# WaldoRevE.net
KiCad netlist of a schematic drawn in EAGLE
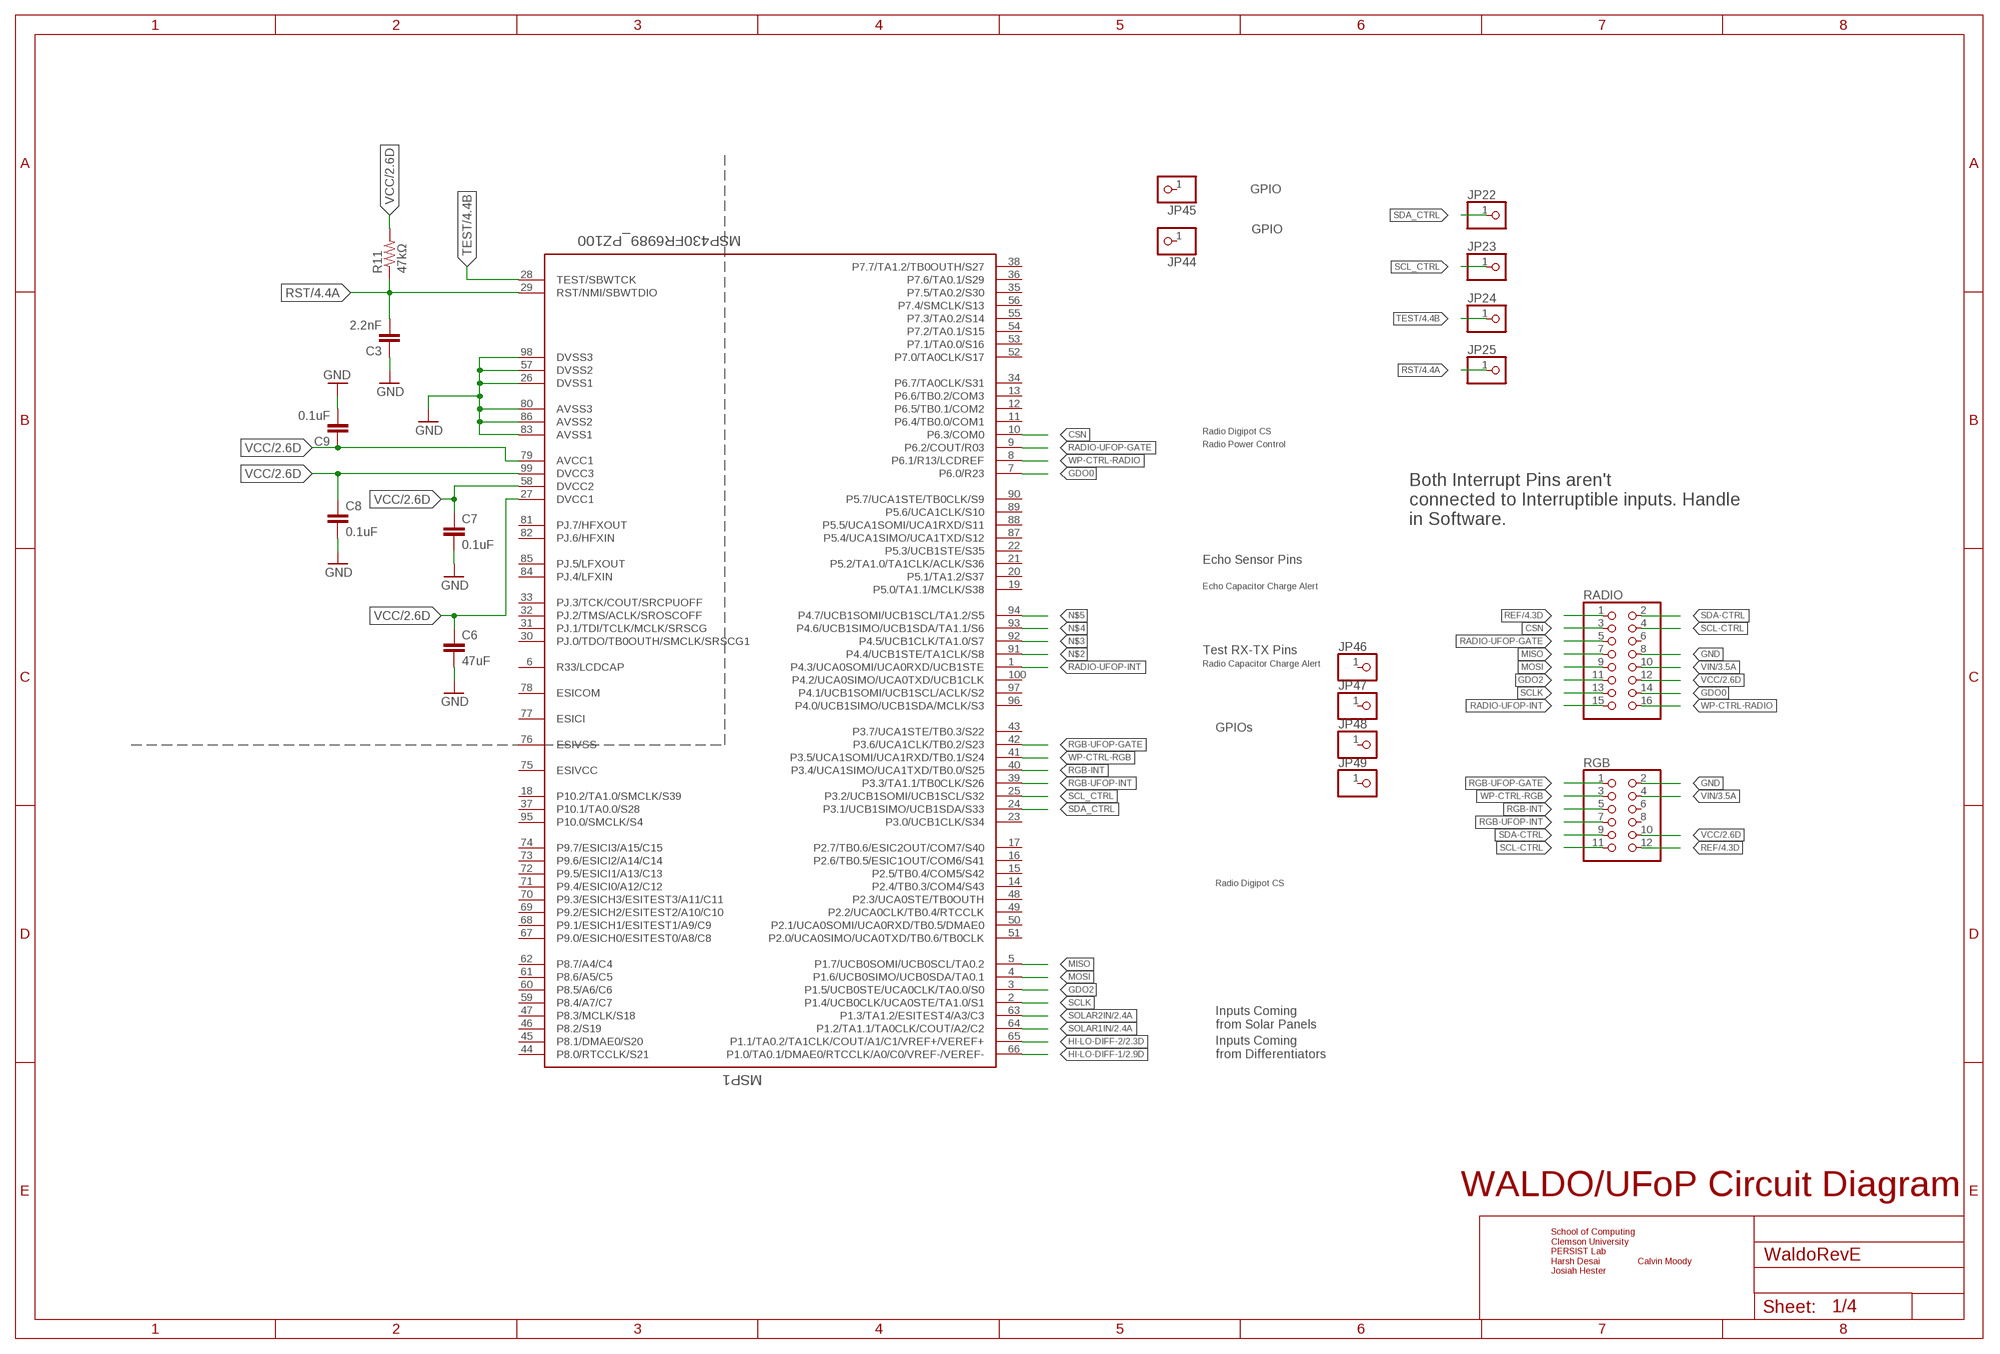
[diagram p0: schematic, sheet 1]
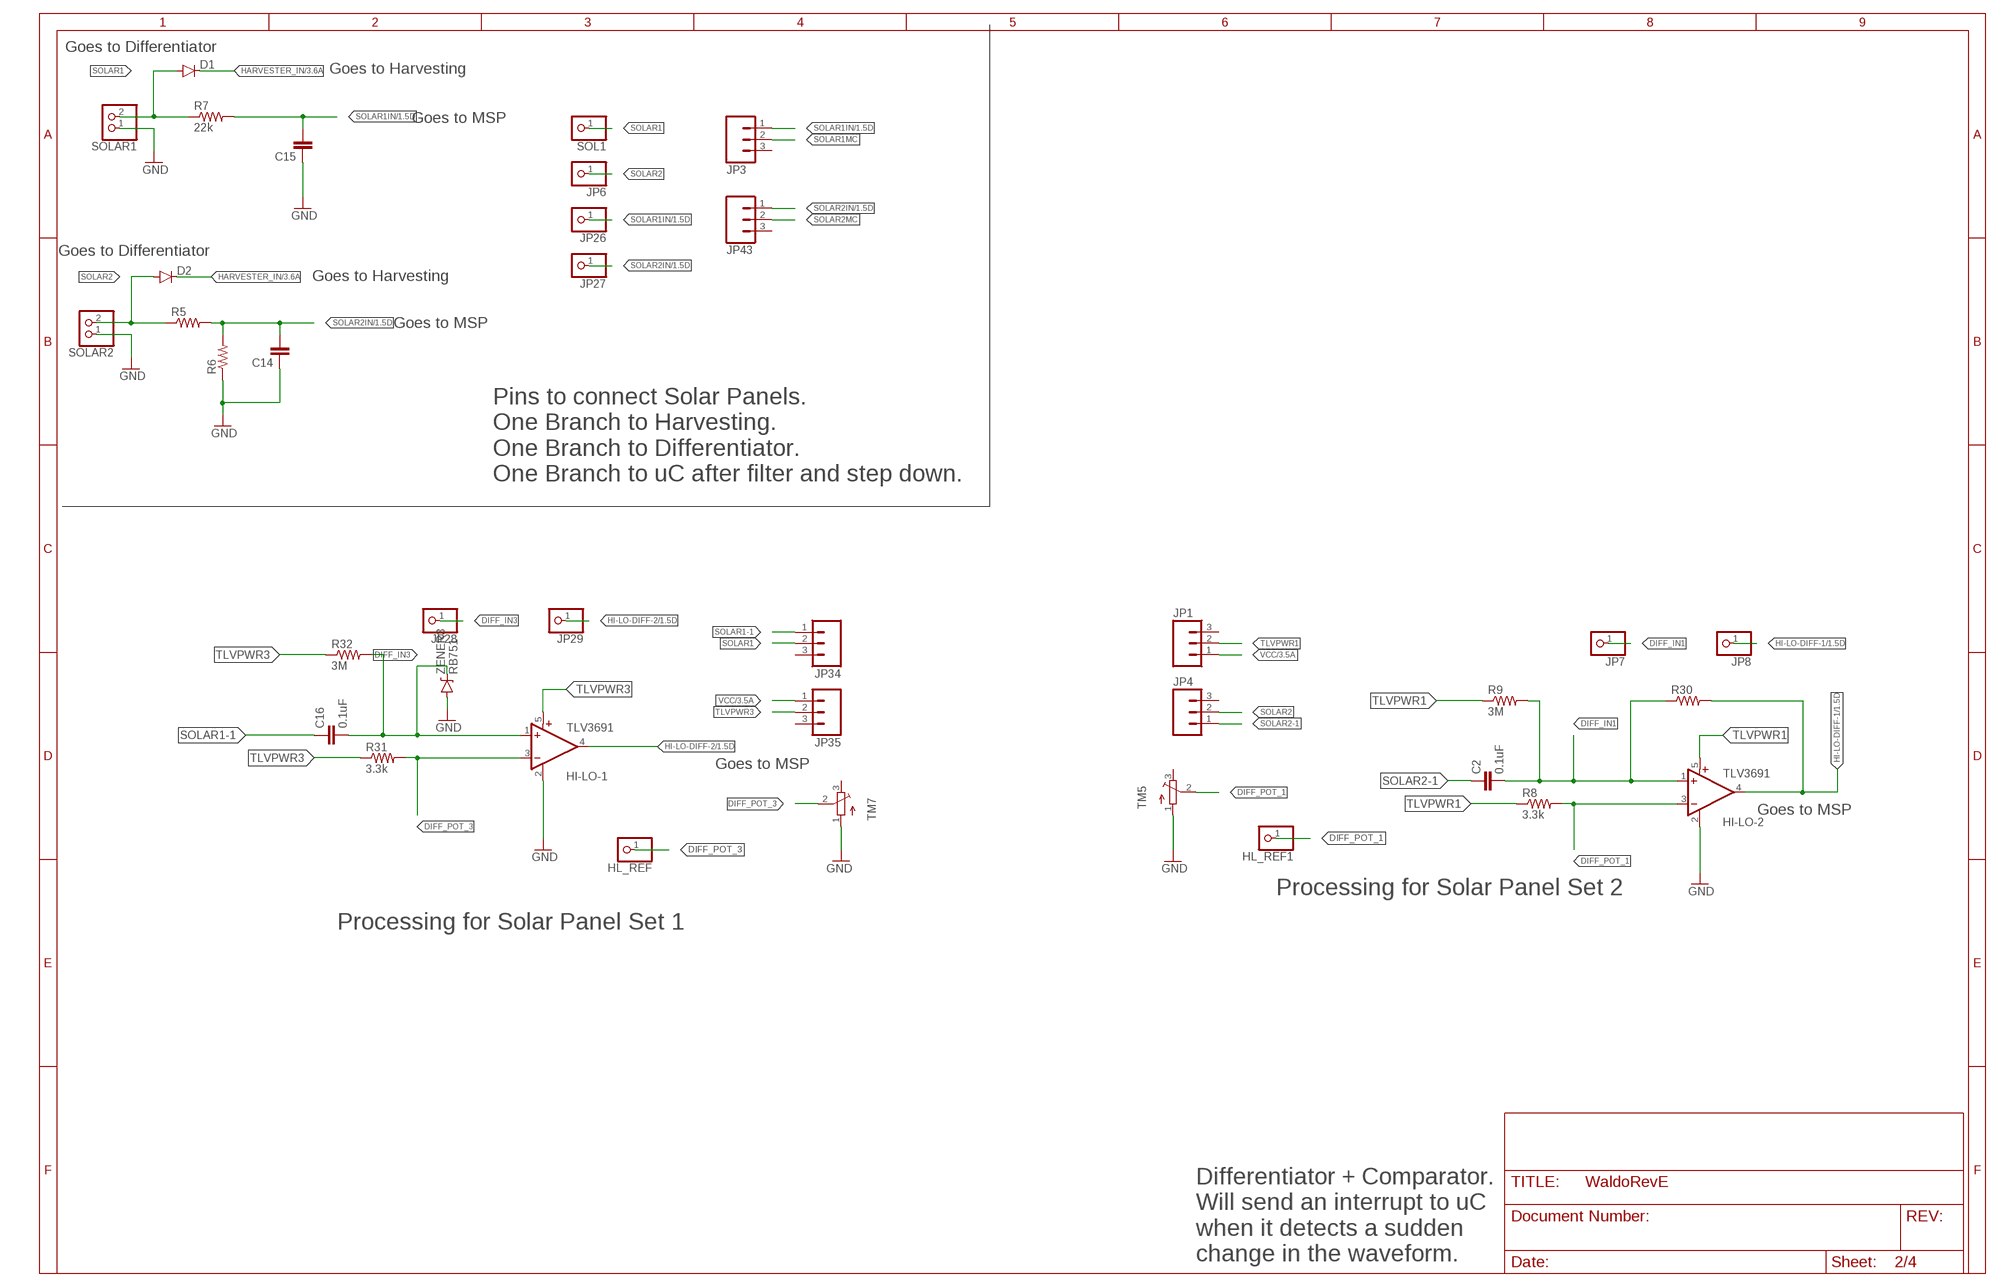
[diagram p1: schematic, sheet 2]
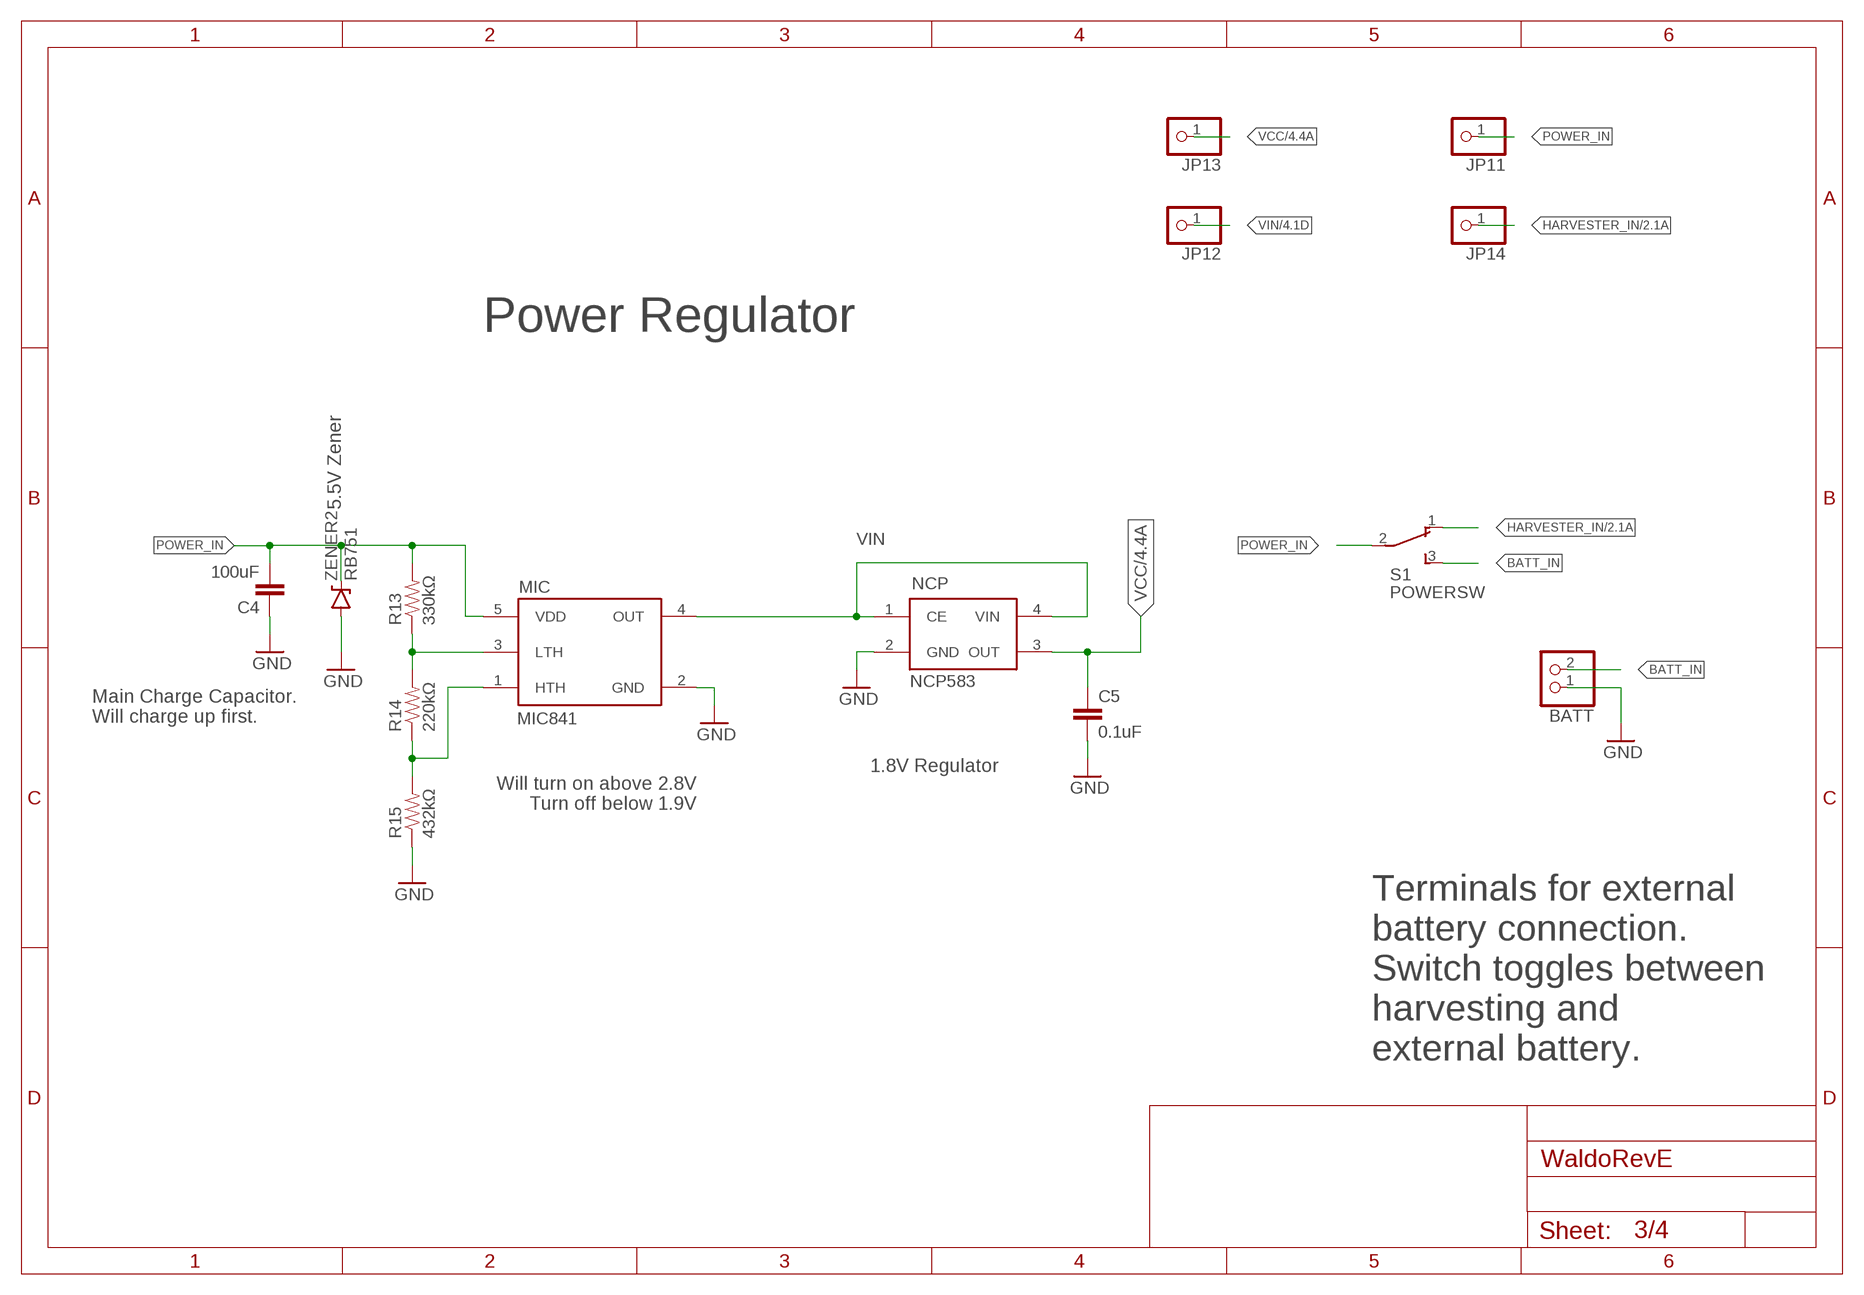
[diagram p2: schematic, sheet 3]
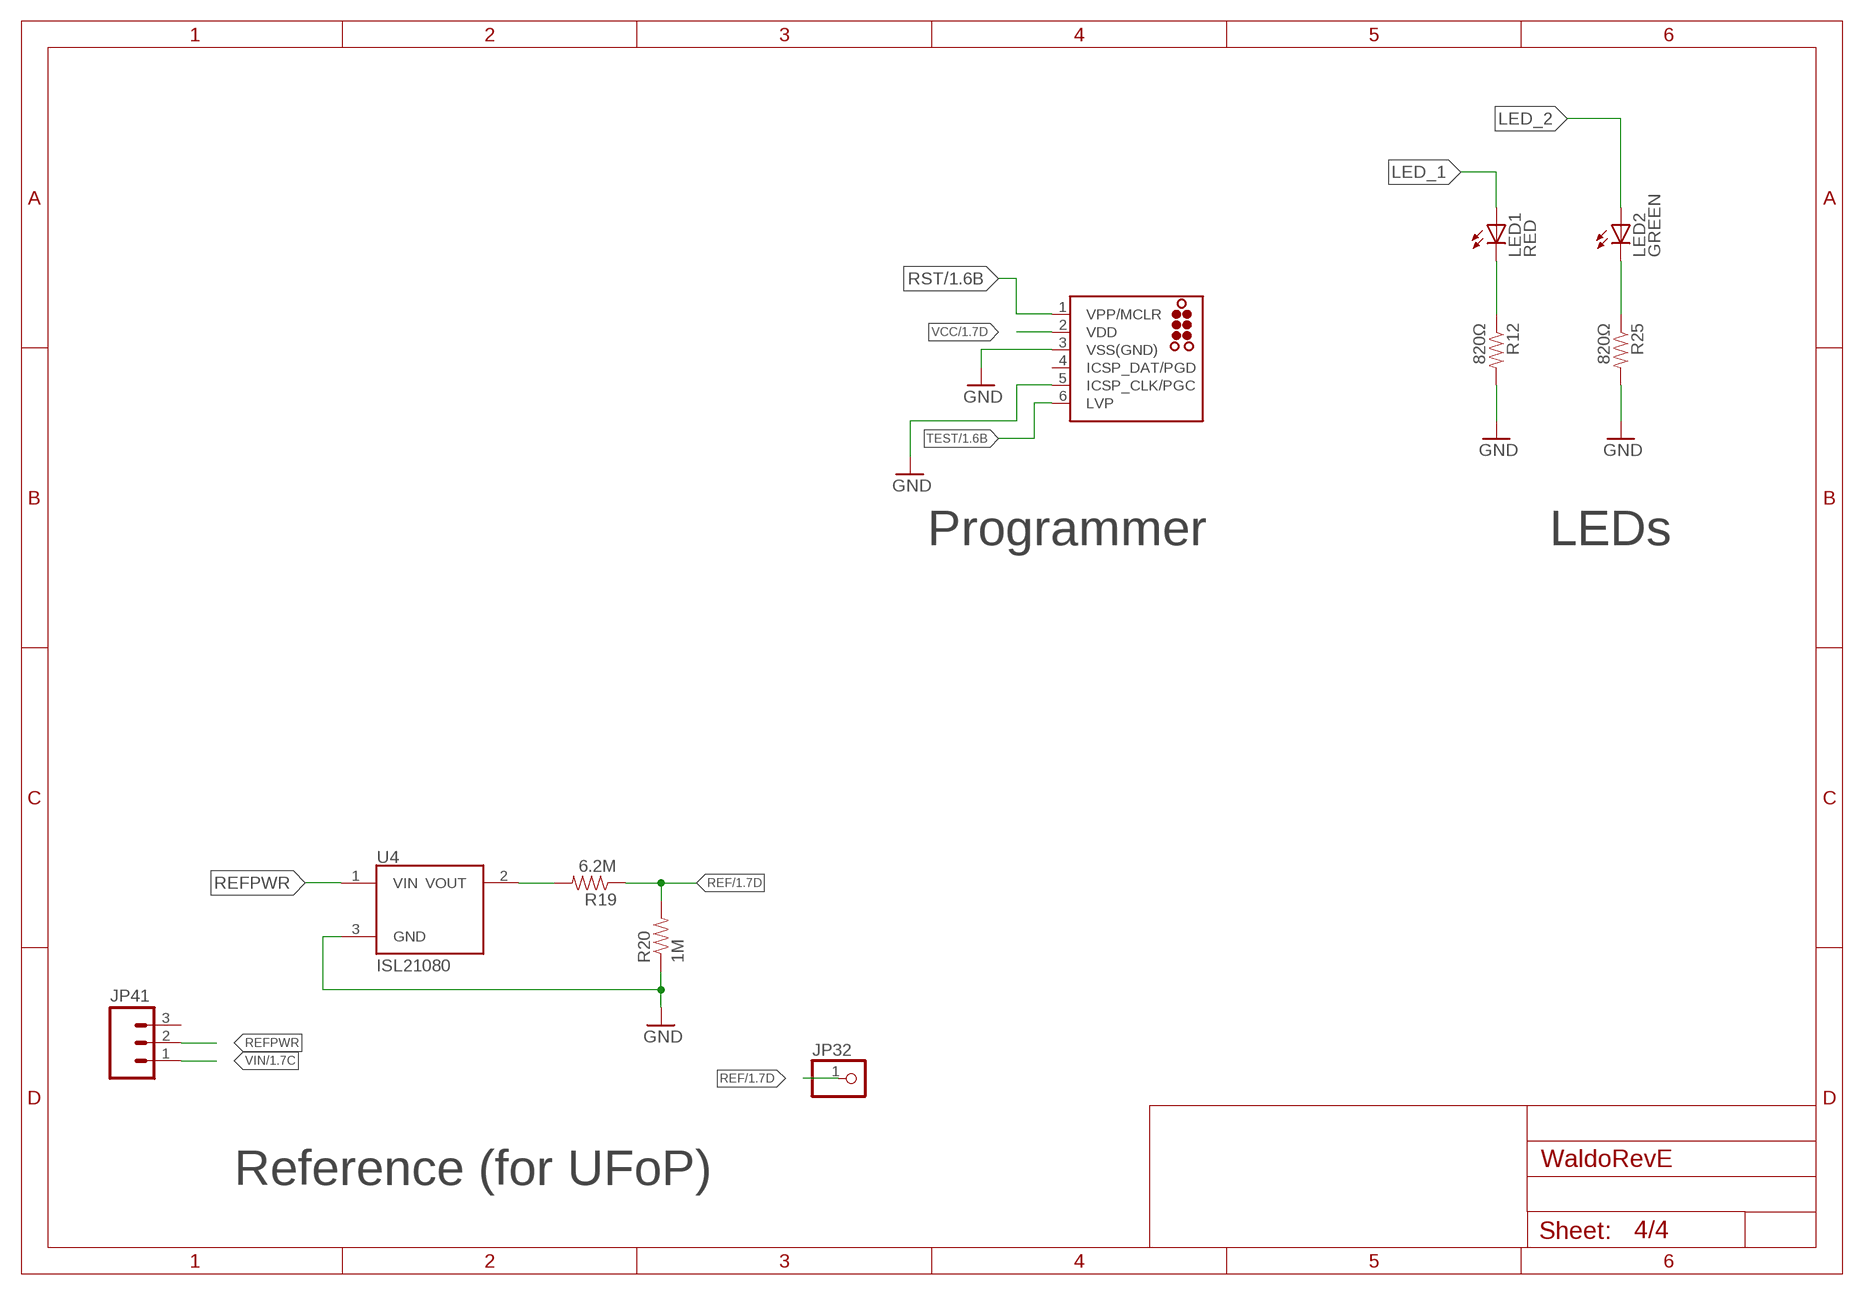
[diagram p3: schematic, sheet 4]

(export (version "E")
  (design (tool "Eeschema 10.0.6"))
  (components
    (comp (ref "C2")
      (value "0.1uF")
      (footprint "eagle-import:0805")
      (libsource (lib "eagle-import") (part "CAP0805"))
    )
    (comp (ref "C14")
      (value "CAP0805")
      (footprint "eagle-import:0805")
      (libsource (lib "eagle-import") (part "CAP0805"))
    )
    (comp (ref "C15")
      (value "CAP0805")
      (footprint "eagle-import:0805")
      (libsource (lib "eagle-import") (part "CAP0805"))
    )
    (comp (ref "C16")
      (value "0.1uF")
      (footprint "eagle-import:0805")
      (libsource (lib "eagle-import") (part "CAP0805"))
    )
    (comp (ref "D1")
      (value "DIODESOD523")
      (footprint "eagle-import:SOD523")
      (libsource (lib "eagle-import") (part "DIODESOD523"))
    )
    (comp (ref "D2")
      (value "DIODESOD523")
      (footprint "eagle-import:SOD523")
      (libsource (lib "eagle-import") (part "DIODESOD523"))
    )
    (comp (ref "HI-LO-1")
      (value "TLV3691")
      (footprint "eagle-import:SC70-5")
      (libsource (lib "eagle-import") (part "TLV3691"))
    )
    (comp (ref "HI-LO-2")
      (value "TLV3691")
      (footprint "eagle-import:SC70-5")
      (libsource (lib "eagle-import") (part "TLV3691"))
    )
    (comp (ref "HL_REF")
      (value "PINHD-1X1")
      (footprint "eagle-import:1X01")
      (libsource (lib "eagle-import") (part "PINHD-1X1"))
    )
    (comp (ref "HL_REF1")
      (value "PINHD-1X1")
      (footprint "eagle-import:1X01")
      (libsource (lib "eagle-import") (part "PINHD-1X1"))
    )
    (comp (ref "JP1")
      (value "M03")
      (footprint "eagle-import:1X03-1.27MM")
      (libsource (lib "eagle-import") (part "M03"))
    )
    (comp (ref "JP3")
      (value "M03")
      (footprint "eagle-import:1X03-1.27MM")
      (libsource (lib "eagle-import") (part "M03"))
    )
    (comp (ref "JP4")
      (value "M03")
      (footprint "eagle-import:1X03-1.27MM")
      (libsource (lib "eagle-import") (part "M03"))
    )
    (comp (ref "JP6")
      (value "PINHD-1X1")
      (footprint "eagle-import:1X01")
      (libsource (lib "eagle-import") (part "PINHD-1X1"))
    )
    (comp (ref "JP7")
      (value "PINHD-1X1")
      (footprint "eagle-import:1X01")
      (libsource (lib "eagle-import") (part "PINHD-1X1"))
    )
    (comp (ref "JP8")
      (value "PINHD-1X1")
      (footprint "eagle-import:1X01")
      (libsource (lib "eagle-import") (part "PINHD-1X1"))
    )
    (comp (ref "JP26")
      (value "PINHD-1X1")
      (footprint "eagle-import:1X01")
      (libsource (lib "eagle-import") (part "PINHD-1X1"))
    )
    (comp (ref "JP27")
      (value "PINHD-1X1")
      (footprint "eagle-import:1X01")
      (libsource (lib "eagle-import") (part "PINHD-1X1"))
    )
    (comp (ref "JP28")
      (value "PINHD-1X1")
      (footprint "eagle-import:1X01")
      (libsource (lib "eagle-import") (part "PINHD-1X1"))
    )
    (comp (ref "JP29")
      (value "PINHD-1X1")
      (footprint "eagle-import:1X01")
      (libsource (lib "eagle-import") (part "PINHD-1X1"))
    )
    (comp (ref "JP34")
      (value "M03")
      (footprint "eagle-import:1X03-1.27MM")
      (libsource (lib "eagle-import") (part "M03"))
    )
    (comp (ref "JP35")
      (value "M03")
      (footprint "eagle-import:1X03-1.27MM")
      (libsource (lib "eagle-import") (part "M03"))
    )
    (comp (ref "JP43")
      (value "M03")
      (footprint "eagle-import:1X03-1.27MM")
      (libsource (lib "eagle-import") (part "M03"))
    )
    (comp (ref "R5")
      (value "RESISTOR0805-RES")
      (footprint "eagle-import:0805")
      (libsource (lib "eagle-import") (part "RESISTOR0805-RES"))
    )
    (comp (ref "R6")
      (value "RESISTOR0805-RES")
      (footprint "eagle-import:0805")
      (libsource (lib "eagle-import") (part "RESISTOR0805-RES"))
    )
    (comp (ref "R7")
      (value "22k")
      (footprint "eagle-import:0805")
      (libsource (lib "eagle-import") (part "RESISTOR0805-RES"))
    )
    (comp (ref "R8")
      (value "3.3k")
      (footprint "eagle-import:0805")
      (libsource (lib "eagle-import") (part "RESISTOR0805-RES"))
    )
    (comp (ref "R9")
      (value "3M")
      (footprint "eagle-import:0805")
      (libsource (lib "eagle-import") (part "RESISTOR0805-RES"))
    )
    (comp (ref "R30")
      (value "RESISTOR0805-RES")
      (footprint "eagle-import:0805")
      (libsource (lib "eagle-import") (part "RESISTOR0805-RES"))
    )
    (comp (ref "R31")
      (value "3.3k")
      (footprint "eagle-import:0805")
      (libsource (lib "eagle-import") (part "RESISTOR0805-RES"))
    )
    (comp (ref "R32")
      (value "3M")
      (footprint "eagle-import:0805")
      (libsource (lib "eagle-import") (part "RESISTOR0805-RES"))
    )
    (comp (ref "SOL1")
      (value "PINHD-1X1")
      (footprint "eagle-import:1X01")
      (libsource (lib "eagle-import") (part "PINHD-1X1"))
    )
    (comp (ref "SOLAR1")
      (value "PINHD-1X2")
      (footprint "eagle-import:1X02")
      (libsource (lib "eagle-import") (part "PINHD-1X2"))
    )
    (comp (ref "SOLAR2")
      (value "PINHD-1X2")
      (footprint "eagle-import:1X02")
      (libsource (lib "eagle-import") (part "PINHD-1X2"))
    )
    (comp (ref "TM5")
      (value "TRIMPOTTC33X")
      (footprint "eagle-import:TC33X")
      (libsource (lib "eagle-import") (part "TRIMPOTTC33X"))
    )
    (comp (ref "TM7")
      (value "TRIMPOTTC33X")
      (footprint "eagle-import:TC33X")
      (libsource (lib "eagle-import") (part "TRIMPOTTC33X"))
    )
    (comp (ref "ZENER3")
      (value "RB751")
      (footprint "eagle-import:SOD-523")
      (libsource (lib "eagle-import") (part "DIODE-ZENER"))
    )
    (comp (ref "C3")
      (value "2.2nF")
      (footprint "eagle-import:0805")
      (libsource (lib "eagle-import") (part "CAP0805"))
    )
    (comp (ref "C6")
      (value "47uF")
      (footprint "eagle-import:0805")
      (libsource (lib "eagle-import") (part "CAP0805"))
    )
    (comp (ref "C7")
      (value "0.1uF")
      (footprint "eagle-import:0805")
      (libsource (lib "eagle-import") (part "CAP0805"))
    )
    (comp (ref "C8")
      (value "0.1uF")
      (footprint "eagle-import:0805")
      (libsource (lib "eagle-import") (part "CAP0805"))
    )
    (comp (ref "C9")
      (value "0.1uF")
      (footprint "eagle-import:0805")
      (libsource (lib "eagle-import") (part "CAP0805"))
    )
    (comp (ref "JP22")
      (value "PINHD-1X1")
      (footprint "eagle-import:1X01")
      (libsource (lib "eagle-import") (part "PINHD-1X1"))
    )
    (comp (ref "JP23")
      (value "PINHD-1X1")
      (footprint "eagle-import:1X01")
      (libsource (lib "eagle-import") (part "PINHD-1X1"))
    )
    (comp (ref "JP24")
      (value "PINHD-1X1")
      (footprint "eagle-import:1X01")
      (libsource (lib "eagle-import") (part "PINHD-1X1"))
    )
    (comp (ref "JP25")
      (value "PINHD-1X1")
      (footprint "eagle-import:1X01")
      (libsource (lib "eagle-import") (part "PINHD-1X1"))
    )
    (comp (ref "JP44")
      (value "PINHD-1X1")
      (footprint "eagle-import:1X01")
      (libsource (lib "eagle-import") (part "PINHD-1X1"))
    )
    (comp (ref "JP45")
      (value "PINHD-1X1")
      (footprint "eagle-import:1X01")
      (libsource (lib "eagle-import") (part "PINHD-1X1"))
    )
    (comp (ref "JP46")
      (value "PINHD-1X1")
      (footprint "eagle-import:1X01")
      (libsource (lib "eagle-import") (part "PINHD-1X1"))
    )
    (comp (ref "JP47")
      (value "PINHD-1X1")
      (footprint "eagle-import:1X01")
      (libsource (lib "eagle-import") (part "PINHD-1X1"))
    )
    (comp (ref "JP48")
      (value "PINHD-1X1")
      (footprint "eagle-import:1X01")
      (libsource (lib "eagle-import") (part "PINHD-1X1"))
    )
    (comp (ref "JP49")
      (value "PINHD-1X1")
      (footprint "eagle-import:1X01")
      (libsource (lib "eagle-import") (part "PINHD-1X1"))
    )
    (comp (ref "MSP1")
      (value "MSP430FR6989_PZ100")
      (footprint "eagle-import:PZ100")
      (libsource (lib "eagle-import") (part "MSP430FR6989_PZ100"))
    )
    (comp (ref "R11")
      (value "47kΩ")
      (footprint "eagle-import:0805")
      (libsource (lib "eagle-import") (part "RESISTOR0805-RES"))
    )
    (comp (ref "RADIO")
      (value "PINHD-2X8/90")
      (footprint "eagle-import:2X08_90")
      (libsource (lib "eagle-import") (part "PINHD-2X8/90"))
    )
    (comp (ref "RGB")
      (value "PINHD-2X6/90")
      (footprint "eagle-import:2X06_90")
      (libsource (lib "eagle-import") (part "PINHD-2X6/90"))
    )
    (comp (ref "J2")
      (value "TC2030-MCP-NL")
      (footprint "eagle-import:TC2030-MCP-NL")
      (libsource (lib "eagle-import") (part "TC2030-MCP-NL"))
    )
    (comp (ref "JP32")
      (value "PINHD-1X1")
      (footprint "eagle-import:1X01")
      (libsource (lib "eagle-import") (part "PINHD-1X1"))
    )
    (comp (ref "JP41")
      (value "M03")
      (footprint "eagle-import:1X03-1.27MM")
      (libsource (lib "eagle-import") (part "M03"))
    )
    (comp (ref "LED1")
      (value "RED")
      (footprint "eagle-import:CHIP-LED0805")
      (libsource (lib "eagle-import") (part "LEDCHIP-LED0805"))
    )
    (comp (ref "LED2")
      (value "GREEN")
      (footprint "eagle-import:CHIP-LED0805")
      (libsource (lib "eagle-import") (part "LEDCHIP-LED0805"))
    )
    (comp (ref "R12")
      (value "820Ω")
      (footprint "eagle-import:0805")
      (libsource (lib "eagle-import") (part "RESISTOR0805-RES"))
    )
    (comp (ref "R19")
      (value "6.2M")
      (footprint "eagle-import:0805")
      (libsource (lib "eagle-import") (part "RESISTOR0805-RES"))
    )
    (comp (ref "R20")
      (value "1M")
      (footprint "eagle-import:0805")
      (libsource (lib "eagle-import") (part "RESISTOR0805-RES"))
    )
    (comp (ref "R25")
      (value "820Ω")
      (footprint "eagle-import:0805")
      (libsource (lib "eagle-import") (part "RESISTOR0805-RES"))
    )
    (comp (ref "U4")
      (value "ISL21080")
      (footprint "eagle-import:SOT-23")
      (libsource (lib "eagle-import") (part "ISL21080"))
    )
    (comp (ref "BATT")
      (value "PINHD-1X2")
      (footprint "eagle-import:1X02")
      (libsource (lib "eagle-import") (part "PINHD-1X2"))
    )
    (comp (ref "C4")
      (value "100uF")
      (footprint "eagle-import:0805")
      (libsource (lib "eagle-import") (part "CAP0805"))
    )
    (comp (ref "C5")
      (value "0.1uF")
      (footprint "eagle-import:0805")
      (libsource (lib "eagle-import") (part "CAP0805"))
    )
    (comp (ref "JP11")
      (value "PINHD-1X1")
      (footprint "eagle-import:1X01")
      (libsource (lib "eagle-import") (part "PINHD-1X1"))
    )
    (comp (ref "JP12")
      (value "PINHD-1X1")
      (footprint "eagle-import:1X01")
      (libsource (lib "eagle-import") (part "PINHD-1X1"))
    )
    (comp (ref "JP13")
      (value "PINHD-1X1")
      (footprint "eagle-import:1X01")
      (libsource (lib "eagle-import") (part "PINHD-1X1"))
    )
    (comp (ref "JP14")
      (value "PINHD-1X1")
      (footprint "eagle-import:1X01")
      (libsource (lib "eagle-import") (part "PINHD-1X1"))
    )
    (comp (ref "MIC")
      (value "MIC841")
      (footprint "eagle-import:SC70-5")
      (libsource (lib "eagle-import") (part "MIC841"))
    )
    (comp (ref "NCP")
      (value "NCP583")
      (footprint "eagle-import:SC82-AB_1PRIMARY")
      (libsource (lib "eagle-import") (part "NCP583"))
    )
    (comp (ref "R13")
      (value "330kΩ")
      (footprint "eagle-import:0805")
      (libsource (lib "eagle-import") (part "RESISTOR0805-RES"))
    )
    (comp (ref "R14")
      (value "220kΩ")
      (footprint "eagle-import:0805")
      (libsource (lib "eagle-import") (part "RESISTOR0805-RES"))
    )
    (comp (ref "R15")
      (value "432kΩ")
      (footprint "eagle-import:0805")
      (libsource (lib "eagle-import") (part "RESISTOR0805-RES"))
    )
    (comp (ref "S1")
      (value "POWERSW")
      (footprint "eagle-import:TL3XYO")
      (libsource (lib "eagle-import") (part "POWERSW"))
    )
    (comp (ref "ZENER2")
      (value "RB751")
      (footprint "eagle-import:SOD-523")
      (libsource (lib "eagle-import") (part "DIODE-ZENER"))
    )
  )
  (nets
    (net (code "1") (name "BATT_IN") (class "Default")
      (node (ref "BATT") (pin "2") (pinfunction "2_2") (pintype "passive"))
      (node (ref "S1") (pin "3") (pinfunction "S_3") (pintype "passive"))
    )
    (net (code "2") (name "CSN") (class "Default")
      (node (ref "MSP1") (pin "10") (pinfunction "P6.3/COM0_10") (pintype "bidirectional"))
      (node (ref "RADIO") (pin "3") (pinfunction "3_3") (pintype "passive"))
    )
    (net (code "3") (name "DIFF_IN1") (class "Default")
      (node (ref "C2") (pin "2") (pinfunction "2_2") (pintype "passive"))
      (node (ref "HI-LO-2") (pin "1") (pinfunction "+IN_1") (pintype "input"))
      (node (ref "JP7") (pin "1") (pinfunction "1_1") (pintype "passive"))
      (node (ref "R30") (pin "1") (pinfunction "1_1") (pintype "passive"))
      (node (ref "R9") (pin "2") (pinfunction "2_2") (pintype "passive"))
    )
    (net (code "4") (name "DIFF_IN3") (class "Default")
      (node (ref "C16") (pin "2") (pinfunction "2_2") (pintype "passive"))
      (node (ref "HI-LO-1") (pin "1") (pinfunction "+IN_1") (pintype "input"))
      (node (ref "JP28") (pin "1") (pinfunction "1_1") (pintype "passive"))
      (node (ref "R32") (pin "2") (pinfunction "2_2") (pintype "passive"))
      (node (ref "ZENER3") (pin "CATHODE") (pinfunction "C_CATHODE") (pintype "passive"))
    )
    (net (code "5") (name "DIFF_POT_1") (class "Default")
      (node (ref "HI-LO-2") (pin "3") (pinfunction "-IN_3") (pintype "input"))
      (node (ref "HL_REF1") (pin "1") (pinfunction "1_1") (pintype "passive"))
      (node (ref "R8") (pin "2") (pinfunction "2_2") (pintype "passive"))
      (node (ref "TM5") (pin "2") (pinfunction "S_2") (pintype "passive"))
    )
    (net (code "6") (name "DIFF_POT_3") (class "Default")
      (node (ref "HI-LO-1") (pin "3") (pinfunction "-IN_3") (pintype "input"))
      (node (ref "HL_REF") (pin "1") (pinfunction "1_1") (pintype "passive"))
      (node (ref "R31") (pin "2") (pinfunction "2_2") (pintype "passive"))
      (node (ref "TM7") (pin "2") (pinfunction "S_2") (pintype "passive"))
    )
    (net (code "7") (name "GDO0") (class "Default")
      (node (ref "MSP1") (pin "7") (pinfunction "P6.0/R23_7") (pintype "bidirectional"))
      (node (ref "RADIO") (pin "14") (pinfunction "14_14") (pintype "passive"))
    )
    (net (code "8") (name "GDO2") (class "Default")
      (node (ref "MSP1") (pin "3") (pinfunction "P1.5/UCB0STE/UCA0CLK/TA0.0/S0_3") (pintype "bidirectional"))
      (node (ref "RADIO") (pin "11") (pinfunction "11_11") (pintype "passive"))
    )
    (net (code "9") (name "GND") (class "Default")
      (node (ref "BATT") (pin "1") (pinfunction "1_1") (pintype "passive"))
      (node (ref "C14") (pin "1") (pinfunction "1_1") (pintype "passive"))
      (node (ref "C15") (pin "1") (pinfunction "1_1") (pintype "passive"))
      (node (ref "C3") (pin "1") (pinfunction "1_1") (pintype "passive"))
      (node (ref "C4") (pin "1") (pinfunction "1_1") (pintype "passive"))
      (node (ref "C5") (pin "2") (pinfunction "2_2") (pintype "passive"))
      (node (ref "C6") (pin "2") (pinfunction "2_2") (pintype "passive"))
      (node (ref "C7") (pin "2") (pinfunction "2_2") (pintype "passive"))
      (node (ref "C8") (pin "2") (pinfunction "2_2") (pintype "passive"))
      (node (ref "C9") (pin "2") (pinfunction "2_2") (pintype "passive"))
      (node (ref "HI-LO-1") (pin "2") (pinfunction "GND_2") (pintype "power_in"))
      (node (ref "HI-LO-2") (pin "2") (pinfunction "GND_2") (pintype "power_in"))
      (node (ref "J2") (pin "3") (pinfunction "VSS(GND)_3") (pintype "power_in"))
      (node (ref "J2") (pin "5") (pinfunction "ICSP_CLK/PGC_5") (pintype "output"))
      (node (ref "MIC") (pin "2") (pinfunction "GND_2") (pintype "bidirectional"))
      (node (ref "MSP1") (pin "26") (pinfunction "DVSS1_26") (pintype "bidirectional"))
      (node (ref "MSP1") (pin "57") (pinfunction "DVSS2_57") (pintype "bidirectional"))
      (node (ref "MSP1") (pin "80") (pinfunction "AVSS3_80") (pintype "bidirectional"))
      (node (ref "MSP1") (pin "83") (pinfunction "AVSS1_83") (pintype "bidirectional"))
      (node (ref "MSP1") (pin "86") (pinfunction "AVSS2_86") (pintype "bidirectional"))
      (node (ref "MSP1") (pin "98") (pinfunction "DVSS3_98") (pintype "bidirectional"))
      (node (ref "NCP") (pin "2") (pinfunction "GND_2") (pintype "bidirectional"))
      (node (ref "R12") (pin "2") (pinfunction "2_2") (pintype "passive"))
      (node (ref "R15") (pin "1") (pinfunction "1_1") (pintype "passive"))
      (node (ref "R20") (pin "1") (pinfunction "1_1") (pintype "passive"))
      (node (ref "R25") (pin "2") (pinfunction "2_2") (pintype "passive"))
      (node (ref "R6") (pin "1") (pinfunction "1_1") (pintype "passive"))
      (node (ref "RADIO") (pin "8") (pinfunction "8_8") (pintype "passive"))
      (node (ref "RGB") (pin "2") (pinfunction "2_2") (pintype "passive"))
      (node (ref "SOLAR1") (pin "1") (pinfunction "1_1") (pintype "passive"))
      (node (ref "SOLAR2") (pin "1") (pinfunction "1_1") (pintype "passive"))
      (node (ref "TM5") (pin "1") (pinfunction "A_1") (pintype "passive"))
      (node (ref "TM7") (pin "1") (pinfunction "A_1") (pintype "passive"))
      (node (ref "U4") (pin "3") (pinfunction "GND_3") (pintype "bidirectional"))
      (node (ref "ZENER2") (pin "ANODE") (pinfunction "A_ANODE") (pintype "passive"))
      (node (ref "ZENER3") (pin "ANODE") (pinfunction "A_ANODE") (pintype "passive"))
    )
    (net (code "10") (name "HARVESTER_IN") (class "Default")
      (node (ref "D1") (pin "C") (pinfunction "C_C") (pintype "passive"))
      (node (ref "D2") (pin "C") (pinfunction "C_C") (pintype "passive"))
      (node (ref "JP14") (pin "1") (pinfunction "1_1") (pintype "passive"))
      (node (ref "S1") (pin "1") (pinfunction "O_1") (pintype "passive"))
    )
    (net (code "11") (name "HI-LO-DIFF-1") (class "Default")
      (node (ref "HI-LO-2") (pin "4") (pinfunction "OUT_4") (pintype "output"))
      (node (ref "JP8") (pin "1") (pinfunction "1_1") (pintype "passive"))
      (node (ref "MSP1") (pin "66") (pinfunction "P1.0/TA0.1/DMAE0/RTCCLK/A0/C0/VREF-/VEREF-_66") (pintype "bidirectional"))
      (node (ref "R30") (pin "2") (pinfunction "2_2") (pintype "passive"))
    )
    (net (code "12") (name "HI-LO-DIFF-2") (class "Default")
      (node (ref "HI-LO-1") (pin "4") (pinfunction "OUT_4") (pintype "output"))
      (node (ref "JP29") (pin "1") (pinfunction "1_1") (pintype "passive"))
      (node (ref "MSP1") (pin "65") (pinfunction "P1.1/TA0.2/TA1CLK/COUT/A1/C1/VREF+/VEREF+_65") (pintype "bidirectional"))
    )
    (net (code "13") (name "LED_1") (class "Default")
      (node (ref "LED1") (pin "A") (pinfunction "A_A") (pintype "passive"))
    )
    (net (code "14") (name "LED_2") (class "Default")
      (node (ref "LED2") (pin "A") (pinfunction "A_A") (pintype "passive"))
    )
    (net (code "15") (name "MISO") (class "Default")
      (node (ref "MSP1") (pin "5") (pinfunction "P1.7/UCB0SOMI/UCB0SCL/TA0.2_5") (pintype "bidirectional"))
      (node (ref "RADIO") (pin "7") (pinfunction "7_7") (pintype "passive"))
    )
    (net (code "16") (name "MOSI") (class "Default")
      (node (ref "MSP1") (pin "4") (pinfunction "P1.6/UCB0SIMO/UCB0SDA/TA0.1_4") (pintype "bidirectional"))
      (node (ref "RADIO") (pin "9") (pinfunction "9_9") (pintype "passive"))
    )
    (net (code "17") (name "N$2") (class "Default")
      (node (ref "MSP1") (pin "91") (pinfunction "P4.4/UCB1STE/TA1CLK/S8_91") (pintype "bidirectional"))
    )
    (net (code "18") (name "N$3") (class "Default")
      (node (ref "MSP1") (pin "92") (pinfunction "P4.5/UCB1CLK/TA1.0/S7_92") (pintype "bidirectional"))
    )
    (net (code "19") (name "N$4") (class "Default")
      (node (ref "MSP1") (pin "93") (pinfunction "P4.6/UCB1SIMO/UCB1SDA/TA1.1/S6_93") (pintype "bidirectional"))
    )
    (net (code "20") (name "N$5") (class "Default")
      (node (ref "MSP1") (pin "94") (pinfunction "P4.7/UCB1SOMI/UCB1SCL/TA1.2/S5_94") (pintype "bidirectional"))
    )
    (net (code "21") (name "Net-(LED1-PadC)") (class "Default")
      (node (ref "LED1") (pin "C") (pinfunction "C_C") (pintype "passive"))
      (node (ref "R12") (pin "1") (pinfunction "1_1") (pintype "passive"))
    )
    (net (code "22") (name "Net-(LED2-PadC)") (class "Default")
      (node (ref "LED2") (pin "C") (pinfunction "C_C") (pintype "passive"))
      (node (ref "R25") (pin "1") (pinfunction "1_1") (pintype "passive"))
    )
    (net (code "23") (name "Net-(MIC-HTH)") (class "Default")
      (node (ref "MIC") (pin "1") (pinfunction "HTH_1") (pintype "bidirectional"))
      (node (ref "R14") (pin "1") (pinfunction "1_1") (pintype "passive"))
      (node (ref "R15") (pin "2") (pinfunction "2_2") (pintype "passive"))
    )
    (net (code "24") (name "Net-(MIC-LTH)") (class "Default")
      (node (ref "MIC") (pin "3") (pinfunction "LTH_3") (pintype "bidirectional"))
      (node (ref "R13") (pin "1") (pinfunction "1_1") (pintype "passive"))
      (node (ref "R14") (pin "2") (pinfunction "2_2") (pintype "passive"))
    )
    (net (code "25") (name "Net-(U4-VOUT)") (class "Default")
      (node (ref "R19") (pin "2") (pinfunction "2_2") (pintype "passive"))
      (node (ref "U4") (pin "2") (pinfunction "VOUT_2") (pintype "bidirectional"))
    )
    (net (code "26") (name "POWER_IN") (class "Default")
      (node (ref "C4") (pin "2") (pinfunction "2_2") (pintype "passive"))
      (node (ref "JP11") (pin "1") (pinfunction "1_1") (pintype "passive"))
      (node (ref "MIC") (pin "5") (pinfunction "VDD_5") (pintype "bidirectional"))
      (node (ref "R13") (pin "2") (pinfunction "2_2") (pintype "passive"))
      (node (ref "S1") (pin "2") (pinfunction "P_2") (pintype "passive"))
      (node (ref "ZENER2") (pin "CATHODE") (pinfunction "C_CATHODE") (pintype "passive"))
    )
    (net (code "27") (name "RADIO-UFOP-GATE") (class "Default")
      (node (ref "MSP1") (pin "9") (pinfunction "P6.2/COUT/R03_9") (pintype "bidirectional"))
      (node (ref "RADIO") (pin "5") (pinfunction "5_5") (pintype "passive"))
    )
    (net (code "28") (name "RADIO-UFOP-INT") (class "Default")
      (node (ref "MSP1") (pin "1") (pinfunction "P4.3/UCA0SOMI/UCA0RXD/UCB1STE_1") (pintype "bidirectional"))
      (node (ref "RADIO") (pin "15") (pinfunction "15_15") (pintype "passive"))
    )
    (net (code "29") (name "REF") (class "Default")
      (node (ref "JP32") (pin "1") (pinfunction "1_1") (pintype "passive"))
      (node (ref "R19") (pin "1") (pinfunction "1_1") (pintype "passive"))
      (node (ref "R20") (pin "2") (pinfunction "2_2") (pintype "passive"))
      (node (ref "RADIO") (pin "1") (pinfunction "1_1") (pintype "passive"))
      (node (ref "RGB") (pin "12") (pinfunction "12_12") (pintype "passive"))
    )
    (net (code "30") (name "REFPWR") (class "Default")
      (node (ref "JP41") (pin "2") (pinfunction "2_2") (pintype "passive"))
      (node (ref "U4") (pin "1") (pinfunction "VIN_1") (pintype "bidirectional"))
    )
    (net (code "31") (name "RGB-INT") (class "Default")
      (node (ref "MSP1") (pin "40") (pinfunction "P3.4/UCA1SIMO/UCA1TXD/TB0.0/S25_40") (pintype "bidirectional"))
      (node (ref "RGB") (pin "5") (pinfunction "5_5") (pintype "passive"))
    )
    (net (code "32") (name "RGB-UFOP-GATE") (class "Default")
      (node (ref "MSP1") (pin "42") (pinfunction "P3.6/UCA1CLK/TB0.2/S23_42") (pintype "bidirectional"))
      (node (ref "RGB") (pin "1") (pinfunction "1_1") (pintype "passive"))
    )
    (net (code "33") (name "RGB-UFOP-INT") (class "Default")
      (node (ref "MSP1") (pin "39") (pinfunction "P3.3/TA1.1/TB0CLK/S26_39") (pintype "bidirectional"))
      (node (ref "RGB") (pin "7") (pinfunction "7_7") (pintype "passive"))
    )
    (net (code "34") (name "RST") (class "Default")
      (node (ref "C3") (pin "2") (pinfunction "2_2") (pintype "passive"))
      (node (ref "J2") (pin "1") (pinfunction "VPP/MCLR_1") (pintype "passive"))
      (node (ref "JP25") (pin "1") (pinfunction "1_1") (pintype "passive"))
      (node (ref "MSP1") (pin "29") (pinfunction "RST/NMI/SBWTDIO_29") (pintype "bidirectional"))
      (node (ref "R11") (pin "1") (pinfunction "1_1") (pintype "passive"))
    )
    (net (code "35") (name "SCL-CTRL") (class "Default")
      (node (ref "RADIO") (pin "4") (pinfunction "4_4") (pintype "passive"))
      (node (ref "RGB") (pin "11") (pinfunction "11_11") (pintype "passive"))
    )
    (net (code "36") (name "SCLK") (class "Default")
      (node (ref "MSP1") (pin "2") (pinfunction "P1.4/UCB0CLK/UCA0STE/TA1.0/S1_2") (pintype "bidirectional"))
      (node (ref "RADIO") (pin "13") (pinfunction "13_13") (pintype "passive"))
    )
    (net (code "37") (name "SCL_CTRL") (class "Default")
      (node (ref "JP23") (pin "1") (pinfunction "1_1") (pintype "passive"))
      (node (ref "MSP1") (pin "25") (pinfunction "P3.2/UCB1SOMI/UCB1SCL/S32_25") (pintype "bidirectional"))
    )
    (net (code "38") (name "SDA-CTRL") (class "Default")
      (node (ref "RADIO") (pin "2") (pinfunction "2_2") (pintype "passive"))
      (node (ref "RGB") (pin "9") (pinfunction "9_9") (pintype "passive"))
    )
    (net (code "39") (name "SDA_CTRL") (class "Default")
      (node (ref "JP22") (pin "1") (pinfunction "1_1") (pintype "passive"))
      (node (ref "MSP1") (pin "24") (pinfunction "P3.1/UCB1SIMO/UCB1SDA/S33_24") (pintype "bidirectional"))
    )
    (net (code "40") (name "SOLAR1") (class "Default")
      (node (ref "D1") (pin "A") (pinfunction "A_A") (pintype "passive"))
      (node (ref "JP34") (pin "2") (pinfunction "2_2") (pintype "passive"))
      (node (ref "R7") (pin "1") (pinfunction "1_1") (pintype "passive"))
      (node (ref "SOL1") (pin "1") (pinfunction "1_1") (pintype "passive"))
      (node (ref "SOLAR1") (pin "2") (pinfunction "2_2") (pintype "passive"))
    )
    (net (code "41") (name "SOLAR1-1") (class "Default")
      (node (ref "C16") (pin "1") (pinfunction "1_1") (pintype "passive"))
      (node (ref "JP34") (pin "1") (pinfunction "1_1") (pintype "passive"))
    )
    (net (code "42") (name "SOLAR1IN") (class "Default")
      (node (ref "C15") (pin "2") (pinfunction "2_2") (pintype "passive"))
      (node (ref "JP26") (pin "1") (pinfunction "1_1") (pintype "passive"))
      (node (ref "JP3") (pin "1") (pinfunction "1_1") (pintype "passive"))
      (node (ref "MSP1") (pin "64") (pinfunction "P1.2/TA1.1/TA0CLK/COUT/A2/C2_64") (pintype "bidirectional"))
      (node (ref "R7") (pin "2") (pinfunction "2_2") (pintype "passive"))
    )
    (net (code "43") (name "SOLAR1MC") (class "Default")
      (node (ref "JP3") (pin "2") (pinfunction "2_2") (pintype "passive"))
    )
    (net (code "44") (name "SOLAR2") (class "Default")
      (node (ref "D2") (pin "A") (pinfunction "A_A") (pintype "passive"))
      (node (ref "JP4") (pin "2") (pinfunction "2_2") (pintype "passive"))
      (node (ref "JP6") (pin "1") (pinfunction "1_1") (pintype "passive"))
      (node (ref "R5") (pin "1") (pinfunction "1_1") (pintype "passive"))
      (node (ref "SOLAR2") (pin "2") (pinfunction "2_2") (pintype "passive"))
    )
    (net (code "45") (name "SOLAR2-1") (class "Default")
      (node (ref "C2") (pin "1") (pinfunction "1_1") (pintype "passive"))
      (node (ref "JP4") (pin "1") (pinfunction "1_1") (pintype "passive"))
    )
    (net (code "46") (name "SOLAR2IN") (class "Default")
      (node (ref "C14") (pin "2") (pinfunction "2_2") (pintype "passive"))
      (node (ref "JP27") (pin "1") (pinfunction "1_1") (pintype "passive"))
      (node (ref "JP43") (pin "1") (pinfunction "1_1") (pintype "passive"))
      (node (ref "MSP1") (pin "63") (pinfunction "P1.3/TA1.2/ESITEST4/A3/C3_63") (pintype "bidirectional"))
      (node (ref "R5") (pin "2") (pinfunction "2_2") (pintype "passive"))
      (node (ref "R6") (pin "2") (pinfunction "2_2") (pintype "passive"))
    )
    (net (code "47") (name "SOLAR2MC") (class "Default")
      (node (ref "JP43") (pin "2") (pinfunction "2_2") (pintype "passive"))
    )
    (net (code "48") (name "TEST") (class "Default")
      (node (ref "J2") (pin "6") (pinfunction "LVP_6") (pintype "bidirectional"))
      (node (ref "JP24") (pin "1") (pinfunction "1_1") (pintype "passive"))
      (node (ref "MSP1") (pin "28") (pinfunction "TEST/SBWTCK_28") (pintype "bidirectional"))
    )
    (net (code "49") (name "TLVPWR1") (class "Default")
      (node (ref "HI-LO-2") (pin "5") (pinfunction "V+_5") (pintype "power_in"))
      (node (ref "JP1") (pin "2") (pinfunction "2_2") (pintype "passive"))
      (node (ref "R8") (pin "1") (pinfunction "1_1") (pintype "passive"))
      (node (ref "R9") (pin "1") (pinfunction "1_1") (pintype "passive"))
    )
    (net (code "50") (name "TLVPWR3") (class "Default")
      (node (ref "HI-LO-1") (pin "5") (pinfunction "V+_5") (pintype "power_in"))
      (node (ref "JP35") (pin "2") (pinfunction "2_2") (pintype "passive"))
      (node (ref "R31") (pin "1") (pinfunction "1_1") (pintype "passive"))
      (node (ref "R32") (pin "1") (pinfunction "1_1") (pintype "passive"))
    )
    (net (code "51") (name "VCC") (class "Default")
      (node (ref "C5") (pin "1") (pinfunction "1_1") (pintype "passive"))
      (node (ref "C6") (pin "1") (pinfunction "1_1") (pintype "passive"))
      (node (ref "C7") (pin "1") (pinfunction "1_1") (pintype "passive"))
      (node (ref "C8") (pin "1") (pinfunction "1_1") (pintype "passive"))
      (node (ref "C9") (pin "1") (pinfunction "1_1") (pintype "passive"))
      (node (ref "J2") (pin "2") (pinfunction "VDD_2") (pintype "power_in"))
      (node (ref "JP1") (pin "1") (pinfunction "1_1") (pintype "passive"))
      (node (ref "JP13") (pin "1") (pinfunction "1_1") (pintype "passive"))
      (node (ref "JP35") (pin "1") (pinfunction "1_1") (pintype "passive"))
      (node (ref "MSP1") (pin "27") (pinfunction "DVCC1_27") (pintype "bidirectional"))
      (node (ref "MSP1") (pin "58") (pinfunction "DVCC2_58") (pintype "bidirectional"))
      (node (ref "MSP1") (pin "79") (pinfunction "AVCC1_79") (pintype "bidirectional"))
      (node (ref "MSP1") (pin "99") (pinfunction "DVCC3_99") (pintype "bidirectional"))
      (node (ref "NCP") (pin "3") (pinfunction "OUT_3") (pintype "bidirectional"))
      (node (ref "R11") (pin "2") (pinfunction "2_2") (pintype "passive"))
      (node (ref "RADIO") (pin "12") (pinfunction "12_12") (pintype "passive"))
      (node (ref "RGB") (pin "10") (pinfunction "10_10") (pintype "passive"))
    )
    (net (code "52") (name "VIN") (class "Default")
      (node (ref "JP12") (pin "1") (pinfunction "1_1") (pintype "passive"))
      (node (ref "JP41") (pin "1") (pinfunction "1_1") (pintype "passive"))
      (node (ref "MIC") (pin "4") (pinfunction "OUT_4") (pintype "bidirectional"))
      (node (ref "NCP") (pin "1") (pinfunction "CE_1") (pintype "bidirectional"))
      (node (ref "NCP") (pin "4") (pinfunction "VIN_4") (pintype "bidirectional"))
      (node (ref "RADIO") (pin "10") (pinfunction "10_10") (pintype "passive"))
      (node (ref "RGB") (pin "4") (pinfunction "4_4") (pintype "passive"))
    )
    (net (code "53") (name "WP-CTRL-RADIO") (class "Default")
      (node (ref "MSP1") (pin "8") (pinfunction "P6.1/R13/LCDREF_8") (pintype "bidirectional"))
      (node (ref "RADIO") (pin "16") (pinfunction "16_16") (pintype "passive"))
    )
    (net (code "54") (name "WP-CTRL-RGB") (class "Default")
      (node (ref "MSP1") (pin "41") (pinfunction "P3.5/UCA1SOMI/UCA1RXD/TB0.1/S24_41") (pintype "bidirectional"))
      (node (ref "RGB") (pin "3") (pinfunction "3_3") (pintype "passive"))
    )
    (net (code "55") (name "unconnected-(J2-ICSP_DAT{slash}PGD-Pad4)") (class "Default")
      (node (ref "J2") (pin "4") (pinfunction "ICSP_DAT/PGD_4") (pintype "bidirectional"))
    )
    (net (code "56") (name "unconnected-(JP1-Pad3)") (class "Default")
      (node (ref "JP1") (pin "3") (pinfunction "3_3") (pintype "passive"))
    )
    (net (code "57") (name "unconnected-(JP3-Pad3)") (class "Default")
      (node (ref "JP3") (pin "3") (pinfunction "3_3") (pintype "passive"))
    )
    (net (code "58") (name "unconnected-(JP4-Pad3)") (class "Default")
      (node (ref "JP4") (pin "3") (pinfunction "3_3") (pintype "passive"))
    )
    (net (code "59") (name "unconnected-(JP34-Pad3)") (class "Default")
      (node (ref "JP34") (pin "3") (pinfunction "3_3") (pintype "passive"))
    )
    (net (code "60") (name "unconnected-(JP35-Pad3)") (class "Default")
      (node (ref "JP35") (pin "3") (pinfunction "3_3") (pintype "passive"))
    )
    (net (code "61") (name "unconnected-(JP41-Pad3)") (class "Default")
      (node (ref "JP41") (pin "3") (pinfunction "3_3") (pintype "passive"))
    )
    (net (code "62") (name "unconnected-(JP43-Pad3)") (class "Default")
      (node (ref "JP43") (pin "3") (pinfunction "3_3") (pintype "passive"))
    )
    (net (code "63") (name "unconnected-(JP44-Pad1)") (class "Default")
      (node (ref "JP44") (pin "1") (pinfunction "1_1") (pintype "passive"))
    )
    (net (code "64") (name "unconnected-(JP45-Pad1)") (class "Default")
      (node (ref "JP45") (pin "1") (pinfunction "1_1") (pintype "passive"))
    )
    (net (code "65") (name "unconnected-(JP46-Pad1)") (class "Default")
      (node (ref "JP46") (pin "1") (pinfunction "1_1") (pintype "passive"))
    )
    (net (code "66") (name "unconnected-(JP47-Pad1)") (class "Default")
      (node (ref "JP47") (pin "1") (pinfunction "1_1") (pintype "passive"))
    )
    (net (code "67") (name "unconnected-(JP48-Pad1)") (class "Default")
      (node (ref "JP48") (pin "1") (pinfunction "1_1") (pintype "passive"))
    )
    (net (code "68") (name "unconnected-(JP49-Pad1)") (class "Default")
      (node (ref "JP49") (pin "1") (pinfunction "1_1") (pintype "passive"))
    )
    (net (code "69") (name "unconnected-(MSP1-ESICI-Pad77)") (class "Default")
      (node (ref "MSP1") (pin "77") (pinfunction "ESICI_77") (pintype "bidirectional"))
    )
    (net (code "70") (name "unconnected-(MSP1-ESICOM-Pad78)") (class "Default")
      (node (ref "MSP1") (pin "78") (pinfunction "ESICOM_78") (pintype "bidirectional"))
    )
    (net (code "71") (name "unconnected-(MSP1-ESIVCC-Pad75)") (class "Default")
      (node (ref "MSP1") (pin "75") (pinfunction "ESIVCC_75") (pintype "bidirectional"))
    )
    (net (code "72") (name "unconnected-(MSP1-ESIVSS-Pad76)") (class "Default")
      (node (ref "MSP1") (pin "76") (pinfunction "ESIVSS_76") (pintype "bidirectional"))
    )
    (net (code "73") (name "unconnected-(MSP1-P2.0{slash}UCA0SIMO{slash}UCA0TXD{slash}TB0.6{slash}TB0CLK-Pad51)") (class "Default")
      (node (ref "MSP1") (pin "51") (pinfunction "P2.0/UCA0SIMO/UCA0TXD/TB0.6/TB0CLK_51") (pintype "bidirectional"))
    )
    (net (code "74") (name "unconnected-(MSP1-P2.1{slash}UCA0SOMI{slash}UCA0RXD{slash}TB0.5{slash}DMAE0-Pad50)") (class "Default")
      (node (ref "MSP1") (pin "50") (pinfunction "P2.1/UCA0SOMI/UCA0RXD/TB0.5/DMAE0_50") (pintype "bidirectional"))
    )
    (net (code "75") (name "unconnected-(MSP1-P2.2{slash}UCA0CLK{slash}TB0.4{slash}RTCCLK-Pad49)") (class "Default")
      (node (ref "MSP1") (pin "49") (pinfunction "P2.2/UCA0CLK/TB0.4/RTCCLK_49") (pintype "bidirectional"))
    )
    (net (code "76") (name "unconnected-(MSP1-P2.3{slash}UCA0STE{slash}TB0OUTH-Pad48)") (class "Default")
      (node (ref "MSP1") (pin "48") (pinfunction "P2.3/UCA0STE/TB0OUTH_48") (pintype "bidirectional"))
    )
    (net (code "77") (name "unconnected-(MSP1-P2.4{slash}TB0.3{slash}COM4{slash}S43-Pad14)") (class "Default")
      (node (ref "MSP1") (pin "14") (pinfunction "P2.4/TB0.3/COM4/S43_14") (pintype "bidirectional"))
    )
    (net (code "78") (name "unconnected-(MSP1-P2.5{slash}TB0.4{slash}COM5{slash}S42-Pad15)") (class "Default")
      (node (ref "MSP1") (pin "15") (pinfunction "P2.5/TB0.4/COM5/S42_15") (pintype "bidirectional"))
    )
    (net (code "79") (name "unconnected-(MSP1-P2.6{slash}TB0.5{slash}ESIC1OUT{slash}COM6{slash}S41-Pad16)") (class "Default")
      (node (ref "MSP1") (pin "16") (pinfunction "P2.6/TB0.5/ESIC1OUT/COM6/S41_16") (pintype "bidirectional"))
    )
    (net (code "80") (name "unconnected-(MSP1-P2.7{slash}TB0.6{slash}ESIC2OUT{slash}COM7{slash}S40-Pad17)") (class "Default")
      (node (ref "MSP1") (pin "17") (pinfunction "P2.7/TB0.6/ESIC2OUT/COM7/S40_17") (pintype "bidirectional"))
    )
    (net (code "81") (name "unconnected-(MSP1-P3.0{slash}UCB1CLK{slash}S34-Pad23)") (class "Default")
      (node (ref "MSP1") (pin "23") (pinfunction "P3.0/UCB1CLK/S34_23") (pintype "bidirectional"))
    )
    (net (code "82") (name "unconnected-(MSP1-P3.7{slash}UCA1STE{slash}TB0.3{slash}S22-Pad43)") (class "Default")
      (node (ref "MSP1") (pin "43") (pinfunction "P3.7/UCA1STE/TB0.3/S22_43") (pintype "bidirectional"))
    )
    (net (code "83") (name "unconnected-(MSP1-P4.0{slash}UCB1SIMO{slash}UCB1SDA{slash}MCLK{slash}S3-Pad96)") (class "Default")
      (node (ref "MSP1") (pin "96") (pinfunction "P4.0/UCB1SIMO/UCB1SDA/MCLK/S3_96") (pintype "bidirectional"))
    )
    (net (code "84") (name "unconnected-(MSP1-P4.1{slash}UCB1SOMI{slash}UCB1SCL{slash}ACLK{slash}S2-Pad97)") (class "Default")
      (node (ref "MSP1") (pin "97") (pinfunction "P4.1/UCB1SOMI/UCB1SCL/ACLK/S2_97") (pintype "bidirectional"))
    )
    (net (code "85") (name "unconnected-(MSP1-P4.2{slash}UCA0SIMO{slash}UCA0TXD{slash}UCB1CLK-Pad100)") (class "Default")
      (node (ref "MSP1") (pin "100") (pinfunction "P4.2/UCA0SIMO/UCA0TXD/UCB1CLK_100") (pintype "bidirectional"))
    )
    (net (code "86") (name "unconnected-(MSP1-P5.0{slash}TA1.1{slash}MCLK{slash}S38-Pad19)") (class "Default")
      (node (ref "MSP1") (pin "19") (pinfunction "P5.0/TA1.1/MCLK/S38_19") (pintype "bidirectional"))
    )
    (net (code "87") (name "unconnected-(MSP1-P5.1{slash}TA1.2{slash}S37-Pad20)") (class "Default")
      (node (ref "MSP1") (pin "20") (pinfunction "P5.1/TA1.2/S37_20") (pintype "bidirectional"))
    )
    (net (code "88") (name "unconnected-(MSP1-P5.2{slash}TA1.0{slash}TA1CLK{slash}ACLK{slash}S36-Pad21)") (class "Default")
      (node (ref "MSP1") (pin "21") (pinfunction "P5.2/TA1.0/TA1CLK/ACLK/S36_21") (pintype "bidirectional"))
    )
    (net (code "89") (name "unconnected-(MSP1-P5.3{slash}UCB1STE{slash}S35-Pad22)") (class "Default")
      (node (ref "MSP1") (pin "22") (pinfunction "P5.3/UCB1STE/S35_22") (pintype "bidirectional"))
    )
    (net (code "90") (name "unconnected-(MSP1-P5.4{slash}UCA1SIMO{slash}UCA1TXD{slash}S12-Pad87)") (class "Default")
      (node (ref "MSP1") (pin "87") (pinfunction "P5.4/UCA1SIMO/UCA1TXD/S12_87") (pintype "bidirectional"))
    )
    (net (code "91") (name "unconnected-(MSP1-P5.5{slash}UCA1SOMI{slash}UCA1RXD{slash}S11-Pad88)") (class "Default")
      (node (ref "MSP1") (pin "88") (pinfunction "P5.5/UCA1SOMI/UCA1RXD/S11_88") (pintype "bidirectional"))
    )
    (net (code "92") (name "unconnected-(MSP1-P5.6{slash}UCA1CLK{slash}S10-Pad89)") (class "Default")
      (node (ref "MSP1") (pin "89") (pinfunction "P5.6/UCA1CLK/S10_89") (pintype "bidirectional"))
    )
    (net (code "93") (name "unconnected-(MSP1-P5.7{slash}UCA1STE{slash}TB0CLK{slash}S9-Pad90)") (class "Default")
      (node (ref "MSP1") (pin "90") (pinfunction "P5.7/UCA1STE/TB0CLK/S9_90") (pintype "bidirectional"))
    )
    (net (code "94") (name "unconnected-(MSP1-P6.4{slash}TB0.0{slash}COM1-Pad11)") (class "Default")
      (node (ref "MSP1") (pin "11") (pinfunction "P6.4/TB0.0/COM1_11") (pintype "bidirectional"))
    )
    (net (code "95") (name "unconnected-(MSP1-P6.5{slash}TB0.1{slash}COM2-Pad12)") (class "Default")
      (node (ref "MSP1") (pin "12") (pinfunction "P6.5/TB0.1/COM2_12") (pintype "bidirectional"))
    )
    (net (code "96") (name "unconnected-(MSP1-P6.6{slash}TB0.2{slash}COM3-Pad13)") (class "Default")
      (node (ref "MSP1") (pin "13") (pinfunction "P6.6/TB0.2/COM3_13") (pintype "bidirectional"))
    )
    (net (code "97") (name "unconnected-(MSP1-P6.7{slash}TA0CLK{slash}S31-Pad34)") (class "Default")
      (node (ref "MSP1") (pin "34") (pinfunction "P6.7/TA0CLK/S31_34") (pintype "bidirectional"))
    )
    (net (code "98") (name "unconnected-(MSP1-P7.0{slash}TA0CLK{slash}S17-Pad52)") (class "Default")
      (node (ref "MSP1") (pin "52") (pinfunction "P7.0/TA0CLK/S17_52") (pintype "bidirectional"))
    )
    (net (code "99") (name "unconnected-(MSP1-P7.1{slash}TA0.0{slash}S16-Pad53)") (class "Default")
      (node (ref "MSP1") (pin "53") (pinfunction "P7.1/TA0.0/S16_53") (pintype "bidirectional"))
    )
    (net (code "100") (name "unconnected-(MSP1-P7.2{slash}TA0.1{slash}S15-Pad54)") (class "Default")
      (node (ref "MSP1") (pin "54") (pinfunction "P7.2/TA0.1/S15_54") (pintype "bidirectional"))
    )
    (net (code "101") (name "unconnected-(MSP1-P7.3{slash}TA0.2{slash}S14-Pad55)") (class "Default")
      (node (ref "MSP1") (pin "55") (pinfunction "P7.3/TA0.2/S14_55") (pintype "bidirectional"))
    )
    (net (code "102") (name "unconnected-(MSP1-P7.4{slash}SMCLK{slash}S13-Pad56)") (class "Default")
      (node (ref "MSP1") (pin "56") (pinfunction "P7.4/SMCLK/S13_56") (pintype "bidirectional"))
    )
    (net (code "103") (name "unconnected-(MSP1-P7.5{slash}TA0.2{slash}S30-Pad35)") (class "Default")
      (node (ref "MSP1") (pin "35") (pinfunction "P7.5/TA0.2/S30_35") (pintype "bidirectional"))
    )
    (net (code "104") (name "unconnected-(MSP1-P7.6{slash}TA0.1{slash}S29-Pad36)") (class "Default")
      (node (ref "MSP1") (pin "36") (pinfunction "P7.6/TA0.1/S29_36") (pintype "bidirectional"))
    )
    (net (code "105") (name "unconnected-(MSP1-P7.7{slash}TA1.2{slash}TB0OUTH{slash}S27-Pad38)") (class "Default")
      (node (ref "MSP1") (pin "38") (pinfunction "P7.7/TA1.2/TB0OUTH/S27_38") (pintype "bidirectional"))
    )
    (net (code "106") (name "unconnected-(MSP1-P8.0{slash}RTCCLK{slash}S21-Pad44)") (class "Default")
      (node (ref "MSP1") (pin "44") (pinfunction "P8.0/RTCCLK/S21_44") (pintype "bidirectional"))
    )
    (net (code "107") (name "unconnected-(MSP1-P8.1{slash}DMAE0{slash}S20-Pad45)") (class "Default")
      (node (ref "MSP1") (pin "45") (pinfunction "P8.1/DMAE0/S20_45") (pintype "bidirectional"))
    )
    (net (code "108") (name "unconnected-(MSP1-P8.2{slash}S19-Pad46)") (class "Default")
      (node (ref "MSP1") (pin "46") (pinfunction "P8.2/S19_46") (pintype "bidirectional"))
    )
    (net (code "109") (name "unconnected-(MSP1-P8.3{slash}MCLK{slash}S18-Pad47)") (class "Default")
      (node (ref "MSP1") (pin "47") (pinfunction "P8.3/MCLK/S18_47") (pintype "bidirectional"))
    )
    (net (code "110") (name "unconnected-(MSP1-P8.4{slash}A7{slash}C7-Pad59)") (class "Default")
      (node (ref "MSP1") (pin "59") (pinfunction "P8.4/A7/C7_59") (pintype "bidirectional"))
    )
    (net (code "111") (name "unconnected-(MSP1-P8.5{slash}A6{slash}C6-Pad60)") (class "Default")
      (node (ref "MSP1") (pin "60") (pinfunction "P8.5/A6/C6_60") (pintype "bidirectional"))
    )
    (net (code "112") (name "unconnected-(MSP1-P8.6{slash}A5{slash}C5-Pad61)") (class "Default")
      (node (ref "MSP1") (pin "61") (pinfunction "P8.6/A5/C5_61") (pintype "bidirectional"))
    )
    (net (code "113") (name "unconnected-(MSP1-P8.7{slash}A4{slash}C4-Pad62)") (class "Default")
      (node (ref "MSP1") (pin "62") (pinfunction "P8.7/A4/C4_62") (pintype "bidirectional"))
    )
    (net (code "114") (name "unconnected-(MSP1-P9.0{slash}ESICH0{slash}ESITEST0{slash}A8{slash}C8-Pad67)") (class "Default")
      (node (ref "MSP1") (pin "67") (pinfunction "P9.0/ESICH0/ESITEST0/A8/C8_67") (pintype "bidirectional"))
    )
    (net (code "115") (name "unconnected-(MSP1-P9.1{slash}ESICH1{slash}ESITEST1{slash}A9{slash}C9-Pad68)") (class "Default")
      (node (ref "MSP1") (pin "68") (pinfunction "P9.1/ESICH1/ESITEST1/A9/C9_68") (pintype "bidirectional"))
    )
    (net (code "116") (name "unconnected-(MSP1-P9.2{slash}ESICH2{slash}ESITEST2{slash}A10{slash}C10-Pad69)") (class "Default")
      (node (ref "MSP1") (pin "69") (pinfunction "P9.2/ESICH2/ESITEST2/A10/C10_69") (pintype "bidirectional"))
    )
    (net (code "117") (name "unconnected-(MSP1-P9.3{slash}ESICH3{slash}ESITEST3{slash}A11{slash}C11-Pad70)") (class "Default")
      (node (ref "MSP1") (pin "70") (pinfunction "P9.3/ESICH3/ESITEST3/A11/C11_70") (pintype "bidirectional"))
    )
    (net (code "118") (name "unconnected-(MSP1-P9.4{slash}ESICI0{slash}A12{slash}C12-Pad71)") (class "Default")
      (node (ref "MSP1") (pin "71") (pinfunction "P9.4/ESICI0/A12/C12_71") (pintype "bidirectional"))
    )
    (net (code "119") (name "unconnected-(MSP1-P9.5{slash}ESICI1{slash}A13{slash}C13-Pad72)") (class "Default")
      (node (ref "MSP1") (pin "72") (pinfunction "P9.5/ESICI1/A13/C13_72") (pintype "bidirectional"))
    )
    (net (code "120") (name "unconnected-(MSP1-P9.6{slash}ESICI2{slash}A14{slash}C14-Pad73)") (class "Default")
      (node (ref "MSP1") (pin "73") (pinfunction "P9.6/ESICI2/A14/C14_73") (pintype "bidirectional"))
    )
    (net (code "121") (name "unconnected-(MSP1-P9.7{slash}ESICI3{slash}A15{slash}C15-Pad74)") (class "Default")
      (node (ref "MSP1") (pin "74") (pinfunction "P9.7/ESICI3/A15/C15_74") (pintype "bidirectional"))
    )
    (net (code "122") (name "unconnected-(MSP1-P10.0{slash}SMCLK{slash}S4-Pad95)") (class "Default")
      (node (ref "MSP1") (pin "95") (pinfunction "P10.0/SMCLK/S4_95") (pintype "bidirectional"))
    )
    (net (code "123") (name "unconnected-(MSP1-P10.1{slash}TA0.0{slash}S28-Pad37)") (class "Default")
      (node (ref "MSP1") (pin "37") (pinfunction "P10.1/TA0.0/S28_37") (pintype "bidirectional"))
    )
    (net (code "124") (name "unconnected-(MSP1-P10.2{slash}TA1.0{slash}SMCLK{slash}S39-Pad18)") (class "Default")
      (node (ref "MSP1") (pin "18") (pinfunction "P10.2/TA1.0/SMCLK/S39_18") (pintype "bidirectional"))
    )
    (net (code "125") (name "unconnected-(MSP1-PJ.0{slash}TDO{slash}TB0OUTH{slash}SMCLK{slash}SRSCG1-Pad30)") (class "Default")
      (node (ref "MSP1") (pin "30") (pinfunction "PJ.0/TDO/TB0OUTH/SMCLK/SRSCG1_30") (pintype "bidirectional"))
    )
    (net (code "126") (name "unconnected-(MSP1-PJ.1{slash}TDI{slash}TCLK{slash}MCLK{slash}SRSCG-Pad31)") (class "Default")
      (node (ref "MSP1") (pin "31") (pinfunction "PJ.1/TDI/TCLK/MCLK/SRSCG_31") (pintype "bidirectional"))
    )
    (net (code "127") (name "unconnected-(MSP1-PJ.2{slash}TMS{slash}ACLK{slash}SROSCOFF-Pad32)") (class "Default")
      (node (ref "MSP1") (pin "32") (pinfunction "PJ.2/TMS/ACLK/SROSCOFF_32") (pintype "bidirectional"))
    )
    (net (code "128") (name "unconnected-(MSP1-PJ.3{slash}TCK{slash}COUT{slash}SRCPUOFF-Pad33)") (class "Default")
      (node (ref "MSP1") (pin "33") (pinfunction "PJ.3/TCK/COUT/SRCPUOFF_33") (pintype "bidirectional"))
    )
    (net (code "129") (name "unconnected-(MSP1-PJ.4{slash}LFXIN-Pad84)") (class "Default")
      (node (ref "MSP1") (pin "84") (pinfunction "PJ.4/LFXIN_84") (pintype "bidirectional"))
    )
    (net (code "130") (name "unconnected-(MSP1-PJ.5{slash}LFXOUT-Pad85)") (class "Default")
      (node (ref "MSP1") (pin "85") (pinfunction "PJ.5/LFXOUT_85") (pintype "bidirectional"))
    )
    (net (code "131") (name "unconnected-(MSP1-PJ.6{slash}HFXIN-Pad82)") (class "Default")
      (node (ref "MSP1") (pin "82") (pinfunction "PJ.6/HFXIN_82") (pintype "bidirectional"))
    )
    (net (code "132") (name "unconnected-(MSP1-PJ.7{slash}HFXOUT-Pad81)") (class "Default")
      (node (ref "MSP1") (pin "81") (pinfunction "PJ.7/HFXOUT_81") (pintype "bidirectional"))
    )
    (net (code "133") (name "unconnected-(MSP1-R33{slash}LCDCAP-Pad6)") (class "Default")
      (node (ref "MSP1") (pin "6") (pinfunction "R33/LCDCAP_6") (pintype "bidirectional"))
    )
    (net (code "134") (name "unconnected-(RADIO-Pad6)") (class "Default")
      (node (ref "RADIO") (pin "6") (pinfunction "6_6") (pintype "passive"))
    )
    (net (code "135") (name "unconnected-(RGB-Pad6)") (class "Default")
      (node (ref "RGB") (pin "6") (pinfunction "6_6") (pintype "passive"))
    )
    (net (code "136") (name "unconnected-(RGB-Pad8)") (class "Default")
      (node (ref "RGB") (pin "8") (pinfunction "8_8") (pintype "passive"))
    )
    (net (code "137") (name "unconnected-(TM5-E-Pad3)") (class "Default")
      (node (ref "TM5") (pin "3") (pinfunction "E_3") (pintype "passive"))
    )
    (net (code "138") (name "unconnected-(TM7-E-Pad3)") (class "Default")
      (node (ref "TM7") (pin "3") (pinfunction "E_3") (pintype "passive"))
    )
  )
)
